# CDCDCDC_3V.net
KiCad netlist of a schematic drawn in Altium Designer
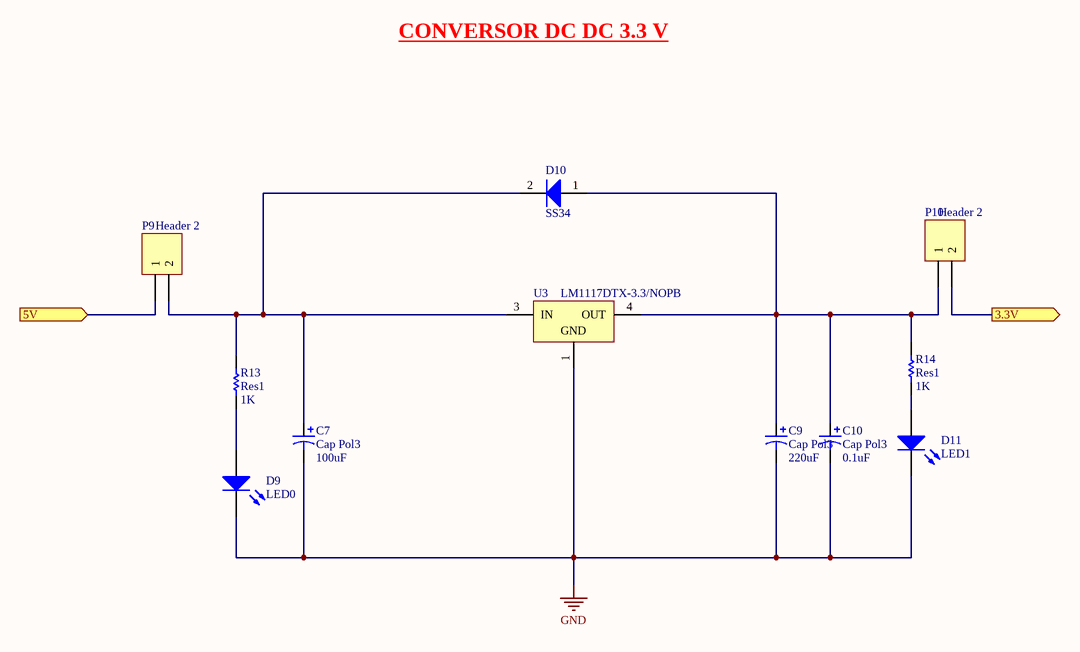
[diagram p0: CDCDCDC_3V.SchDoc]

(export (version "E")
  (design (tool "Eeschema 10.0.6"))
  (components
    (comp (ref "C7")
      (value "Cap Pol3")
      (footprint "1812")
      (description "Polarized Capacitor (Surface Mount)")
      (fields (field (name "ALTIUM_VALUE") "100uF") (field (name "PUBLISHER") "Altium Limited"))
      (libsource (lib "Miscellaneous Devices") (part "Cap Pol3"))
    )
    (comp (ref "C9")
      (value "Cap Pol3")
      (footprint "1812")
      (description "Polarized Capacitor (Surface Mount)")
      (fields (field (name "ALTIUM_VALUE") "220uF") (field (name "PUBLISHER") "Altium Limited"))
      (libsource (lib "Miscellaneous Devices") (part "Cap Pol3"))
    )
    (comp (ref "C10")
      (value "Cap Pol3")
      (footprint "1812")
      (description "Polarized Capacitor (Surface Mount)")
      (fields (field (name "ALTIUM_VALUE") "0.1uF") (field (name "PUBLISHER") "Altium Limited"))
      (libsource (lib "Miscellaneous Devices") (part "Cap Pol3"))
    )
    (comp (ref "D9")
      (value "LED0")
      (footprint "LED-0")
      (description "Typical INFRARED GaAs LED")
      (fields (field (name "PUBLISHER") "Altium Limited"))
      (libsource (lib "Miscellaneous Devices") (part "LED0"))
    )
    (comp (ref "D10")
      (value "SS34")
      (footprint "SMC")
      (description "Default Diode")
      (fields (field (name "PUBLISHER") "Altium Limited"))
      (libsource (lib "Miscellaneous Devices") (part "Diode"))
    )
    (comp (ref "D11")
      (value "LED1")
      (footprint "LED-0")
      (description "Typical INFRARED GaAs LED")
      (fields (field (name "PUBLISHER") "Altium Limited"))
      (libsource (lib "Miscellaneous Devices") (part "LED0"))
    )
    (comp (ref "P9")
      (value "Header 2")
      (footprint "HDR1X2")
      (description "Header, 2-Pin")
      (fields (field (name "PUBLISHER") "Altium Limited"))
      (libsource (lib "Miscellaneous Connectors") (part "Header 2"))
    )
    (comp (ref "P10")
      (value "Header 2")
      (footprint "HDR1X2")
      (description "Header, 2-Pin")
      (fields (field (name "PUBLISHER") "Altium Limited"))
      (libsource (lib "Miscellaneous Connectors") (part "Header 2"))
    )
    (comp (ref "R13")
      (value "Res1")
      (footprint "AXIAL-0.3")
      (description "Resistor")
      (fields (field (name "ALTIUM_VALUE") "1K") (field (name "PUBLISHER") "Altium Limited"))
      (libsource (lib "Miscellaneous Devices") (part "Res1"))
    )
    (comp (ref "R14")
      (value "Res1")
      (footprint "AXIAL-0.3")
      (description "Resistor")
      (fields (field (name "ALTIUM_VALUE") "1K") (field (name "PUBLISHER") "Altium Limited"))
      (libsource (lib "Miscellaneous Devices") (part "Res1"))
    )
    (comp (ref "U3")
      (value "LM1117DTX-3.3/NOPB")
      (footprint "NDP0003B_L")
      (description "800mA Low-Dropout Linear Regulator, 3-pin TO-252, Pb-Free")
      (fields (field (name "MANUFACTURER") "Texas Instruments"))
      (libsource (lib "Schlib1") (part "CMP-0062-00704-3"))
    )
  )
  (nets
    (net (code "1") (name "/3.3V") (class "Default")
      (node (ref "P10") (pin "2") (pinfunction "2_2") (pintype "passive"))
    )
    (net (code "2") (name "/5V") (class "Default")
      (node (ref "P9") (pin "1") (pinfunction "1_1") (pintype "passive"))
    )
    (net (code "3") (name "GND") (class "Default")
      (node (ref "C10") (pin "2") (pinfunction "2_2") (pintype "passive"))
      (node (ref "C7") (pin "2") (pinfunction "2_2") (pintype "passive"))
      (node (ref "C9") (pin "2") (pinfunction "2_2") (pintype "passive"))
      (node (ref "D11") (pin "2") (pinfunction "K_2") (pintype "passive"))
      (node (ref "D9") (pin "2") (pinfunction "K_2") (pintype "passive"))
      (node (ref "U3") (pin "1") (pinfunction "GND_1") (pintype "power_in"))
    )
    (net (code "4") (name "Net-(D9-A)") (class "Default")
      (node (ref "D9") (pin "1") (pinfunction "A_1") (pintype "passive"))
      (node (ref "R13") (pin "1") (pinfunction "1_1") (pintype "passive"))
    )
    (net (code "5") (name "Net-(D10-A)") (class "Default")
      (node (ref "C10") (pin "1") (pinfunction "1_1") (pintype "passive"))
      (node (ref "C9") (pin "1") (pinfunction "1_1") (pintype "passive"))
      (node (ref "D10") (pin "1") (pinfunction "A_1") (pintype "passive"))
      (node (ref "P10") (pin "1") (pinfunction "1_1") (pintype "passive"))
      (node (ref "R14") (pin "2") (pinfunction "2_2") (pintype "passive"))
      (node (ref "U3") (pin "4") (pinfunction "OUT_4") (pintype "power_in"))
    )
    (net (code "6") (name "Net-(D10-K)") (class "Default")
      (node (ref "C7") (pin "1") (pinfunction "1_1") (pintype "passive"))
      (node (ref "D10") (pin "2") (pinfunction "K_2") (pintype "passive"))
      (node (ref "P9") (pin "2") (pinfunction "2_2") (pintype "passive"))
      (node (ref "R13") (pin "2") (pinfunction "2_2") (pintype "passive"))
      (node (ref "U3") (pin "3") (pinfunction "IN_3") (pintype "power_in"))
    )
    (net (code "7") (name "Net-(D11-A)") (class "Default")
      (node (ref "D11") (pin "1") (pinfunction "A_1") (pintype "passive"))
      (node (ref "R14") (pin "1") (pinfunction "1_1") (pintype "passive"))
    )
  )
)
